# BAT_18650X2.net
KiCad netlist of a schematic drawn in Altium Designer
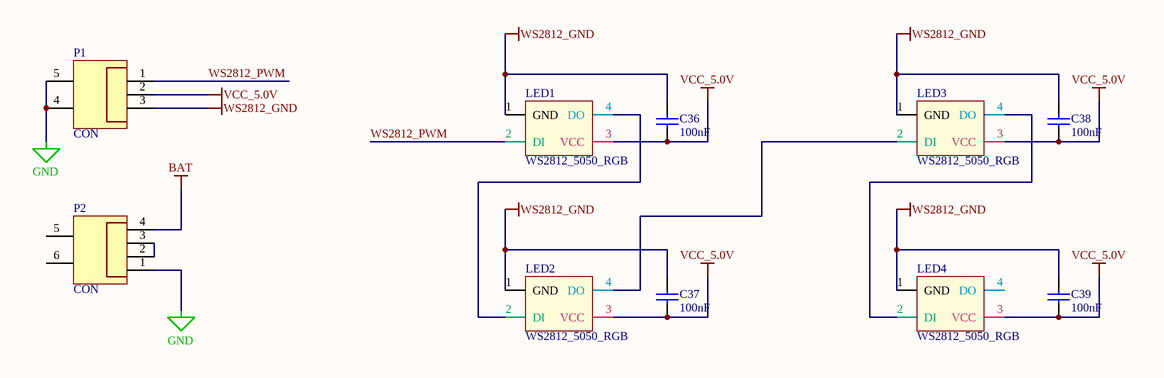
[diagram p0: BAT_18650X2.SchDoc]

(export (version "E")
  (design (tool "Eeschema 10.0.6"))
  (components
    (comp (ref "C36")
      (value "100nF")
      (footprint "0402_C")
      (description "Capacitor")
      (fields (field (name "PUBLISHER") "Altium Limited"))
      (libsource (lib "Cap") (part "Cap"))
    )
    (comp (ref "C37")
      (value "100nF")
      (footprint "0402_C")
      (description "Capacitor")
      (fields (field (name "PUBLISHER") "Altium Limited"))
      (libsource (lib "Cap") (part "Cap"))
    )
    (comp (ref "C38")
      (value "100nF")
      (footprint "0402_C")
      (description "Capacitor")
      (fields (field (name "PUBLISHER") "Altium Limited"))
      (libsource (lib "Cap") (part "Cap"))
    )
    (comp (ref "C39")
      (value "100nF")
      (footprint "0402_C")
      (description "Capacitor")
      (fields (field (name "PUBLISHER") "Altium Limited"))
      (libsource (lib "Cap") (part "Cap"))
    )
    (comp (ref "LED1")
      (value "WS2812_5050_RGB")
      (footprint "RGB_50X50")
      (libsource (lib "WS2812_5050_RGB") (part "WS2812_5050_RGB"))
    )
    (comp (ref "LED2")
      (value "WS2812_5050_RGB")
      (footprint "RGB_50X50")
      (libsource (lib "WS2812_5050_RGB") (part "WS2812_5050_RGB"))
    )
    (comp (ref "LED3")
      (value "WS2812_5050_RGB")
      (footprint "RGB_50X50")
      (libsource (lib "WS2812_5050_RGB") (part "WS2812_5050_RGB"))
    )
    (comp (ref "LED4")
      (value "WS2812_5050_RGB")
      (footprint "RGB_50X50")
      (libsource (lib "WS2812_5050_RGB") (part "WS2812_5050_RGB"))
    )
    (comp (ref "P1") (value "CON") (footprint "BM03B-GHS-TBT(TOP)") (libsource (lib "CON-3") (part "CON-3")))
    (comp (ref "P2") (value "CON") (footprint "18650X2") (libsource (lib "CON-4") (part "CON-4")))
  )
  (nets
    (net (code "1") (name "/WS2812_PWM") (class "Default")
      (node (ref "LED1") (pin "2") (pinfunction "DI_2") (pintype "passive"))
      (node (ref "P1") (pin "1") (pintype "passive"))
    )
    (net (code "2") (name "BAT") (class "Default") (node (ref "P2") (pin "4") (pintype "passive")))
    (net (code "3") (name "GND") (class "Default")
      (node (ref "P1") (pin "4") (pintype "passive"))
      (node (ref "P1") (pin "5") (pintype "passive"))
      (node (ref "P2") (pin "1") (pintype "passive"))
    )
    (net (code "4") (name "Net-(LED1-DO)") (class "Default")
      (node (ref "LED1") (pin "4") (pinfunction "DO_4") (pintype "passive"))
      (node (ref "LED2") (pin "2") (pinfunction "DI_2") (pintype "passive"))
    )
    (net (code "5") (name "Net-(LED2-DO)") (class "Default")
      (node (ref "LED2") (pin "4") (pinfunction "DO_4") (pintype "passive"))
      (node (ref "LED3") (pin "2") (pinfunction "DI_2") (pintype "passive"))
    )
    (net (code "6") (name "Net-(LED3-DO)") (class "Default")
      (node (ref "LED3") (pin "4") (pinfunction "DO_4") (pintype "passive"))
      (node (ref "LED4") (pin "2") (pinfunction "DI_2") (pintype "passive"))
    )
    (net (code "7") (name "Net-(P2-Pad2)") (class "Default")
      (node (ref "P2") (pin "2") (pintype "passive"))
      (node (ref "P2") (pin "3") (pintype "passive"))
    )
    (net (code "8") (name "VCC_5.0V") (class "Default")
      (node (ref "C36") (pin "2") (pinfunction "2_2") (pintype "passive"))
      (node (ref "C37") (pin "2") (pinfunction "2_2") (pintype "passive"))
      (node (ref "C38") (pin "2") (pinfunction "2_2") (pintype "passive"))
      (node (ref "C39") (pin "2") (pinfunction "2_2") (pintype "passive"))
      (node (ref "LED1") (pin "3") (pinfunction "VCC_3") (pintype "passive"))
      (node (ref "LED2") (pin "3") (pinfunction "VCC_3") (pintype "passive"))
      (node (ref "LED3") (pin "3") (pinfunction "VCC_3") (pintype "passive"))
      (node (ref "LED4") (pin "3") (pinfunction "VCC_3") (pintype "passive"))
      (node (ref "P1") (pin "2") (pintype "passive"))
    )
    (net (code "9") (name "WS2812_GND") (class "Default")
      (node (ref "C36") (pin "1") (pinfunction "1_1") (pintype "passive"))
      (node (ref "C37") (pin "1") (pinfunction "1_1") (pintype "passive"))
      (node (ref "C38") (pin "1") (pinfunction "1_1") (pintype "passive"))
      (node (ref "C39") (pin "1") (pinfunction "1_1") (pintype "passive"))
      (node (ref "LED1") (pin "1") (pinfunction "GND_1") (pintype "passive"))
      (node (ref "LED2") (pin "1") (pinfunction "GND_1") (pintype "passive"))
      (node (ref "LED3") (pin "1") (pinfunction "GND_1") (pintype "passive"))
      (node (ref "LED4") (pin "1") (pinfunction "GND_1") (pintype "passive"))
      (node (ref "P1") (pin "3") (pintype "passive"))
    )
    (net (code "10") (name "unconnected-(LED4-DO-Pad4)") (class "Default")
      (node (ref "LED4") (pin "4") (pinfunction "DO_4") (pintype "passive"))
    )
    (net (code "11") (name "unconnected-(P2-Pad5)") (class "Default")
      (node (ref "P2") (pin "5") (pintype "passive"))
    )
    (net (code "12") (name "unconnected-(P2-Pad6)") (class "Default")
      (node (ref "P2") (pin "6") (pintype "passive"))
    )
  )
)
